# MidiWah.net
KiCad netlist of a schematic drawn in EAGLE
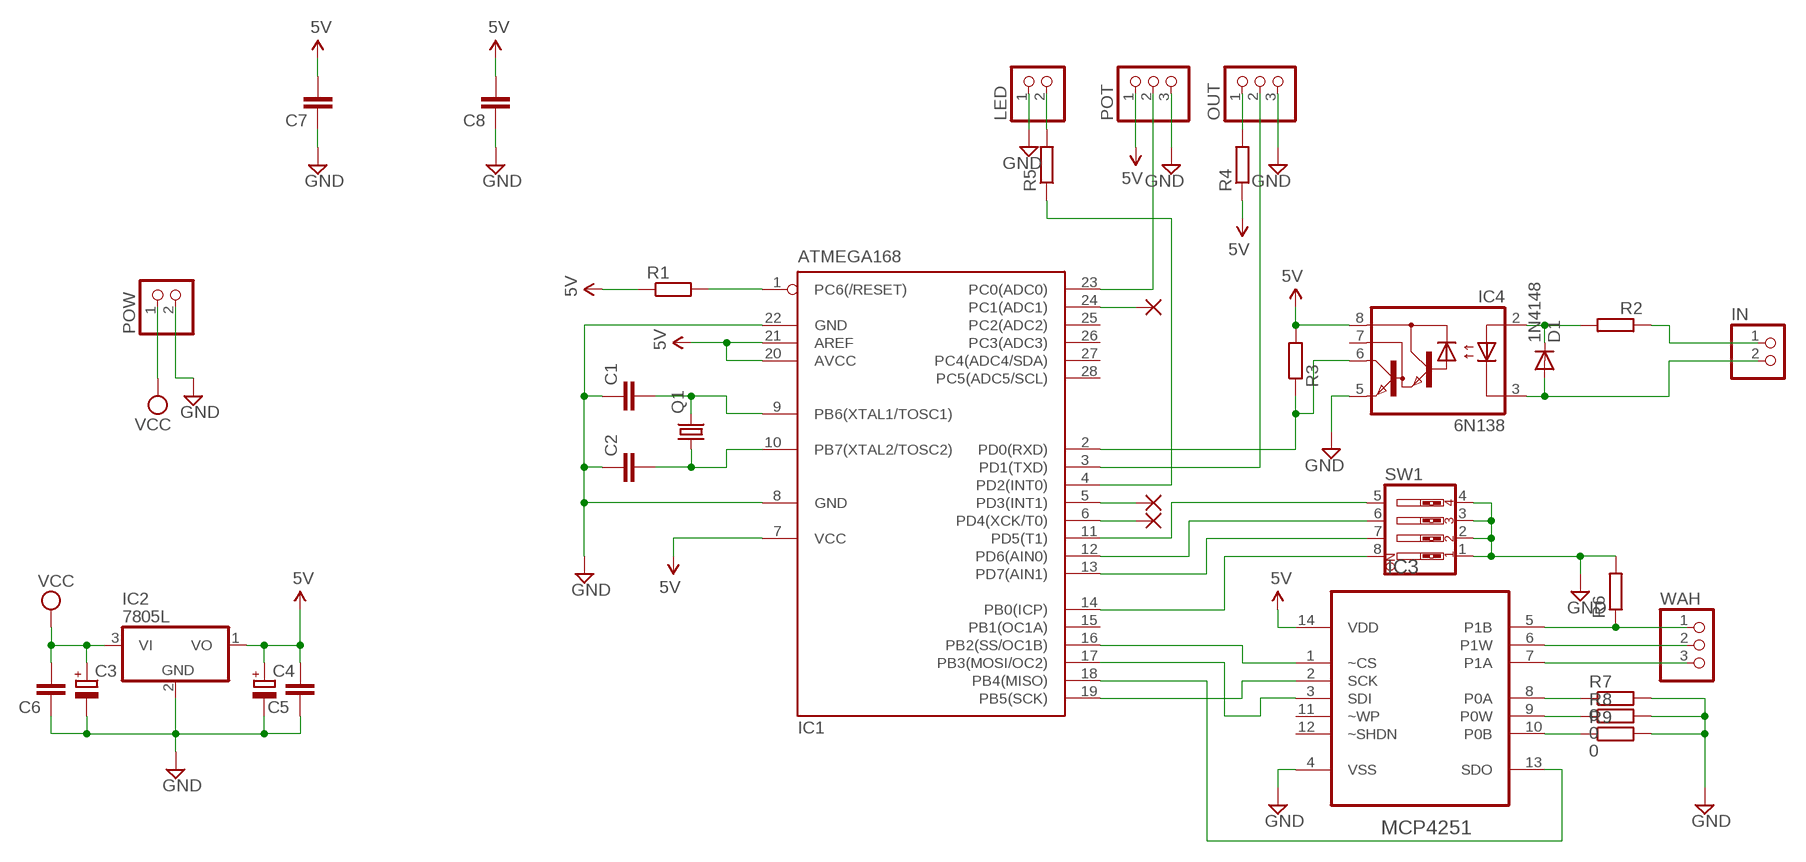
[diagram p0: schematic, sheet 1]

(export (version "E")
  (design (tool "Eeschema 10.0.6"))
  (components
    (comp (ref "C1")
      (value "C-EU025-024X044")
      (footprint "eagle-import:C025-024X044")
      (libsource (lib "eagle-import") (part "C-EU025-024X044"))
    )
    (comp (ref "C2")
      (value "C-EU025-024X044")
      (footprint "eagle-import:C025-024X044")
      (libsource (lib "eagle-import") (part "C-EU025-024X044"))
    )
    (comp (ref "C3")
      (value "CPOL-EUE2.5-5")
      (footprint "eagle-import:E2,5-5")
      (libsource (lib "eagle-import") (part "CPOL-EUE2.5-5"))
    )
    (comp (ref "C4")
      (value "CPOL-EUE2.5-5")
      (footprint "eagle-import:E2,5-5")
      (libsource (lib "eagle-import") (part "CPOL-EUE2.5-5"))
    )
    (comp (ref "C5")
      (value "C-EU025-024X044")
      (footprint "eagle-import:C025-024X044")
      (libsource (lib "eagle-import") (part "C-EU025-024X044"))
    )
    (comp (ref "C6")
      (value "C-EU025-024X044")
      (footprint "eagle-import:C025-024X044")
      (libsource (lib "eagle-import") (part "C-EU025-024X044"))
    )
    (comp (ref "C7")
      (value "C-EU025-024X044")
      (footprint "eagle-import:C025-024X044")
      (libsource (lib "eagle-import") (part "C-EU025-024X044"))
    )
    (comp (ref "C8")
      (value "C-EU025-024X044")
      (footprint "eagle-import:C025-024X044")
      (libsource (lib "eagle-import") (part "C-EU025-024X044"))
    )
    (comp (ref "D1")
      (value "1N4148")
      (footprint "eagle-import:DO35-7")
      (libsource (lib "eagle-import") (part "1N4148DO35-7"))
    )
    (comp (ref "IC1")
      (value "ATMEGA168")
      (footprint "eagle-import:DIL28-3")
      (libsource (lib "eagle-import") (part "MEGA8-P"))
    )
    (comp (ref "IC2")
      (value "7805L")
      (footprint "eagle-import:TO92")
      (libsource (lib "eagle-import") (part "78L05"))
    )
    (comp (ref "IC3")
      (value "MCP4251")
      (footprint "eagle-import:DIP254P762X533-14")
      (fields (field (name "MPN") "MCP4251-104E/P"))
      (libsource (lib "eagle-import") (part "MCP4251-104E/P"))
    )
    (comp (ref "IC4")
      (value "6N138")
      (footprint "eagle-import:DIL08")
      (fields (field (name "MF") "VISHAY/TELEFUNKEN"))
      (libsource (lib "eagle-import") (part "6N138"))
    )
    (comp (ref "IN")
      (value "PINHD-1X2")
      (footprint "eagle-import:1X02")
      (libsource (lib "eagle-import") (part "PINHD-1X2"))
    )
    (comp (ref "LED")
      (value "PINHD-1X2")
      (footprint "eagle-import:1X02")
      (libsource (lib "eagle-import") (part "PINHD-1X2"))
    )
    (comp (ref "OUT")
      (value "PINHD-1X3")
      (footprint "eagle-import:1X03")
      (libsource (lib "eagle-import") (part "PINHD-1X3"))
    )
    (comp (ref "PAD1")
      (value "WIREPAD1,6/0,8")
      (footprint "eagle-import:1,6_0,8")
      (libsource (lib "eagle-import") (part "WIREPAD1,6/0,8"))
    )
    (comp (ref "PAD2")
      (value "WIREPAD1,6/0,8")
      (footprint "eagle-import:1,6_0,8")
      (libsource (lib "eagle-import") (part "WIREPAD1,6/0,8"))
    )
    (comp (ref "PAD3")
      (value "WIREPAD1,6/0,8")
      (footprint "eagle-import:1,6_0,8")
      (libsource (lib "eagle-import") (part "WIREPAD1,6/0,8"))
    )
    (comp (ref "POT")
      (value "PINHD-1X3")
      (footprint "eagle-import:1X03")
      (libsource (lib "eagle-import") (part "PINHD-1X3"))
    )
    (comp (ref "POW")
      (value "PINHD-1X2")
      (footprint "eagle-import:1X02")
      (libsource (lib "eagle-import") (part "PINHD-1X2"))
    )
    (comp (ref "Q1")
      (value "CRYSTALHC49S")
      (footprint "eagle-import:HC49_S")
      (libsource (lib "eagle-import") (part "CRYSTALHC49S"))
    )
    (comp (ref "R1")
      (value "R-EU_0204/7")
      (footprint "eagle-import:0204_7")
      (libsource (lib "eagle-import") (part "R-EU_0204/7"))
    )
    (comp (ref "R2")
      (value "R-EU_0204/7")
      (footprint "eagle-import:0204_7")
      (libsource (lib "eagle-import") (part "R-EU_0204/7"))
    )
    (comp (ref "R3")
      (value "R-EU_0204/7")
      (footprint "eagle-import:0204_7")
      (libsource (lib "eagle-import") (part "R-EU_0204/7"))
    )
    (comp (ref "R4")
      (value "R-EU_0204/7")
      (footprint "eagle-import:0204_7")
      (libsource (lib "eagle-import") (part "R-EU_0204/7"))
    )
    (comp (ref "R5")
      (value "R-EU_0204/7")
      (footprint "eagle-import:0204_7")
      (libsource (lib "eagle-import") (part "R-EU_0204/7"))
    )
    (comp (ref "R6")
      (value "R-EU_0204/2V")
      (footprint "eagle-import:0204V")
      (libsource (lib "eagle-import") (part "R-EU_0204/2V"))
    )
    (comp (ref "R7")
      (value "0")
      (footprint "eagle-import:M0805")
      (libsource (lib "eagle-import") (part "R-EU_M0805"))
    )
    (comp (ref "R8")
      (value "0")
      (footprint "eagle-import:M0805")
      (libsource (lib "eagle-import") (part "R-EU_M0805"))
    )
    (comp (ref "R9")
      (value "0")
      (footprint "eagle-import:M0805")
      (libsource (lib "eagle-import") (part "R-EU_M0805"))
    )
    (comp (ref "SW1")
      (value "SW_DIP-4")
      (footprint "eagle-import:EDG-04")
      (libsource (lib "eagle-import") (part "SW_DIP-4"))
    )
    (comp (ref "WAH")
      (value "PINHD-1X3")
      (footprint "eagle-import:1X03")
      (libsource (lib "eagle-import") (part "PINHD-1X3"))
    )
  )
  (nets
    (net (code "1") (name "5V") (class "Default")
      (node (ref "C4") (pin "+") (pinfunction "+_+") (pintype "passive"))
      (node (ref "C5") (pin "2") (pinfunction "2_2") (pintype "passive"))
      (node (ref "C7") (pin "2") (pinfunction "2_2") (pintype "passive"))
      (node (ref "C8") (pin "2") (pinfunction "2_2") (pintype "passive"))
      (node (ref "IC1") (pin "20") (pinfunction "AVCC_20") (pintype "power_in"))
      (node (ref "IC1") (pin "21") (pinfunction "AREF_21") (pintype "passive"))
      (node (ref "IC1") (pin "7") (pinfunction "VCC_7") (pintype "power_in"))
      (node (ref "IC2") (pin "1") (pinfunction "VO_1") (pintype "passive"))
      (node (ref "IC3") (pin "14") (pinfunction "VDD_14") (pintype "power_in"))
      (node (ref "IC4") (pin "8") (pinfunction "VCC_8") (pintype "passive"))
      (node (ref "POT") (pin "1") (pinfunction "1_1") (pintype "passive"))
      (node (ref "R1") (pin "1") (pinfunction "1_1") (pintype "passive"))
      (node (ref "R3") (pin "2") (pinfunction "2_2") (pintype "passive"))
      (node (ref "R4") (pin "1") (pinfunction "1_1") (pintype "passive"))
    )
    (net (code "2") (name "GND") (class "Default")
      (node (ref "C1") (pin "1") (pinfunction "1_1") (pintype "passive"))
      (node (ref "C2") (pin "1") (pinfunction "1_1") (pintype "passive"))
      (node (ref "C3") (pin "-") (pinfunction "-_-") (pintype "passive"))
      (node (ref "C4") (pin "-") (pinfunction "-_-") (pintype "passive"))
      (node (ref "C5") (pin "1") (pinfunction "1_1") (pintype "passive"))
      (node (ref "C6") (pin "1") (pinfunction "1_1") (pintype "passive"))
      (node (ref "C7") (pin "1") (pinfunction "1_1") (pintype "passive"))
      (node (ref "C8") (pin "1") (pinfunction "1_1") (pintype "passive"))
      (node (ref "IC1") (pin "22") (pinfunction "GND_22") (pintype "power_in"))
      (node (ref "IC1") (pin "8") (pinfunction "GND_8") (pintype "power_in"))
      (node (ref "IC2") (pin "2") (pinfunction "GND_2") (pintype "passive"))
      (node (ref "IC3") (pin "4") (pinfunction "VSS_4") (pintype "power_in"))
      (node (ref "IC4") (pin "5") (pinfunction "GND_5") (pintype "passive"))
      (node (ref "LED") (pin "1") (pinfunction "1_1") (pintype "passive"))
      (node (ref "OUT") (pin "3") (pinfunction "3_3") (pintype "passive"))
      (node (ref "POT") (pin "3") (pinfunction "3_3") (pintype "passive"))
      (node (ref "POW") (pin "2") (pinfunction "2_2") (pintype "passive"))
      (node (ref "R6") (pin "2") (pinfunction "2_2") (pintype "passive"))
      (node (ref "R7") (pin "2") (pinfunction "2_2") (pintype "passive"))
      (node (ref "R8") (pin "2") (pinfunction "2_2") (pintype "passive"))
      (node (ref "R9") (pin "2") (pinfunction "2_2") (pintype "passive"))
      (node (ref "SW1") (pin "1") (pinfunction "1_1") (pintype "passive"))
      (node (ref "SW1") (pin "2") (pinfunction "2_2") (pintype "passive"))
      (node (ref "SW1") (pin "3") (pinfunction "3_3") (pintype "passive"))
      (node (ref "SW1") (pin "4") (pinfunction "4_4") (pintype "passive"))
    )
    (net (code "3") (name "Net-(IC1-PB0(ICP))") (class "Default")
      (node (ref "IC1") (pin "14") (pinfunction "PB0(ICP)_14") (pintype "bidirectional"))
      (node (ref "SW1") (pin "8") (pinfunction "8_8") (pintype "passive"))
    )
    (net (code "4") (name "Net-(IC1-PB2(SS{slash}OC1B))") (class "Default")
      (node (ref "IC1") (pin "16") (pinfunction "PB2(SS/OC1B)_16") (pintype "bidirectional"))
      (node (ref "IC3") (pin "1") (pinfunction "~{CS}_1") (pintype "input"))
    )
    (net (code "5") (name "Net-(IC1-PB3(MOSI{slash}OC2))") (class "Default")
      (node (ref "IC1") (pin "17") (pinfunction "PB3(MOSI/OC2)_17") (pintype "bidirectional"))
      (node (ref "IC3") (pin "3") (pinfunction "SDI_3") (pintype "input"))
    )
    (net (code "6") (name "Net-(IC1-PB4(MISO))") (class "Default")
      (node (ref "IC1") (pin "18") (pinfunction "PB4(MISO)_18") (pintype "bidirectional"))
      (node (ref "IC3") (pin "13") (pinfunction "SDO_13") (pintype "output"))
    )
    (net (code "7") (name "Net-(IC1-PB5(SCK))") (class "Default")
      (node (ref "IC1") (pin "19") (pinfunction "PB5(SCK)_19") (pintype "bidirectional"))
      (node (ref "IC3") (pin "2") (pinfunction "SCK_2") (pintype "input"))
    )
    (net (code "8") (name "Net-(IC1-PB6(XTAL1{slash}TOSC1))") (class "Default")
      (node (ref "C1") (pin "2") (pinfunction "2_2") (pintype "passive"))
      (node (ref "IC1") (pin "9") (pinfunction "PB6(XTAL1/TOSC1)_9") (pintype "bidirectional"))
      (node (ref "Q1") (pin "2") (pinfunction "2_2") (pintype "passive"))
    )
    (net (code "9") (name "Net-(IC1-PB7(XTAL2{slash}TOSC2))") (class "Default")
      (node (ref "C2") (pin "2") (pinfunction "2_2") (pintype "passive"))
      (node (ref "IC1") (pin "10") (pinfunction "PB7(XTAL2/TOSC2)_10") (pintype "bidirectional"))
      (node (ref "Q1") (pin "1") (pinfunction "1_1") (pintype "passive"))
    )
    (net (code "10") (name "Net-(IC1-PC0(ADC0))") (class "Default")
      (node (ref "IC1") (pin "23") (pinfunction "PC0(ADC0)_23") (pintype "bidirectional"))
      (node (ref "POT") (pin "2") (pinfunction "2_2") (pintype "passive"))
    )
    (net (code "11") (name "Net-(IC1-PC1(ADC1))") (class "Default")
      (node (ref "IC1") (pin "24") (pinfunction "PC1(ADC1)_24") (pintype "bidirectional"))
      (node (ref "PAD1") (pin "1") (pinfunction "P_1") (pintype "passive"))
    )
    (net (code "12") (name "Net-(IC1-PC6({slash}RESET))") (class "Default")
      (node (ref "IC1") (pin "1") (pinfunction "PC6(/RESET)_1") (pintype "bidirectional"))
      (node (ref "R1") (pin "2") (pinfunction "2_2") (pintype "passive"))
    )
    (net (code "13") (name "Net-(IC1-PD0(RXD))") (class "Default")
      (node (ref "IC1") (pin "2") (pinfunction "PD0(RXD)_2") (pintype "bidirectional"))
      (node (ref "IC4") (pin "6") (pinfunction "VO_6") (pintype "passive"))
      (node (ref "R3") (pin "1") (pinfunction "1_1") (pintype "passive"))
    )
    (net (code "14") (name "Net-(IC1-PD1(TXD))") (class "Default")
      (node (ref "IC1") (pin "3") (pinfunction "PD1(TXD)_3") (pintype "bidirectional"))
      (node (ref "OUT") (pin "2") (pinfunction "2_2") (pintype "passive"))
    )
    (net (code "15") (name "Net-(IC1-PD2(INT0))") (class "Default")
      (node (ref "IC1") (pin "4") (pinfunction "PD2(INT0)_4") (pintype "bidirectional"))
      (node (ref "R5") (pin "1") (pinfunction "1_1") (pintype "passive"))
    )
    (net (code "16") (name "Net-(IC1-PD3(INT1))") (class "Default")
      (node (ref "IC1") (pin "5") (pinfunction "PD3(INT1)_5") (pintype "bidirectional"))
      (node (ref "PAD2") (pin "1") (pinfunction "P_1") (pintype "passive"))
    )
    (net (code "17") (name "Net-(IC1-PD4(XCK{slash}T0))") (class "Default")
      (node (ref "IC1") (pin "6") (pinfunction "PD4(XCK/T0)_6") (pintype "bidirectional"))
      (node (ref "PAD3") (pin "1") (pinfunction "P_1") (pintype "passive"))
    )
    (net (code "18") (name "Net-(IC1-PD5(T1))") (class "Default")
      (node (ref "IC1") (pin "11") (pinfunction "PD5(T1)_11") (pintype "bidirectional"))
      (node (ref "SW1") (pin "5") (pinfunction "5_5") (pintype "passive"))
    )
    (net (code "19") (name "Net-(IC1-PD6(AIN0))") (class "Default")
      (node (ref "IC1") (pin "12") (pinfunction "PD6(AIN0)_12") (pintype "bidirectional"))
      (node (ref "SW1") (pin "6") (pinfunction "6_6") (pintype "passive"))
    )
    (net (code "20") (name "Net-(IC1-PD7(AIN1))") (class "Default")
      (node (ref "IC1") (pin "13") (pinfunction "PD7(AIN1)_13") (pintype "bidirectional"))
      (node (ref "SW1") (pin "7") (pinfunction "7_7") (pintype "passive"))
    )
    (net (code "21") (name "Net-(IC3-P0A)") (class "Default")
      (node (ref "IC3") (pin "8") (pinfunction "P0A_8") (pintype "passive"))
      (node (ref "R7") (pin "1") (pinfunction "1_1") (pintype "passive"))
    )
    (net (code "22") (name "Net-(IC3-P0B)") (class "Default")
      (node (ref "IC3") (pin "10") (pinfunction "P0B_10") (pintype "passive"))
      (node (ref "R9") (pin "1") (pinfunction "1_1") (pintype "passive"))
    )
    (net (code "23") (name "Net-(IC3-P0W)") (class "Default")
      (node (ref "IC3") (pin "9") (pinfunction "P0W_9") (pintype "passive"))
      (node (ref "R8") (pin "1") (pinfunction "1_1") (pintype "passive"))
    )
    (net (code "24") (name "Net-(IC3-P1A)") (class "Default")
      (node (ref "IC3") (pin "7") (pinfunction "P1A_7") (pintype "passive"))
      (node (ref "WAH") (pin "3") (pinfunction "3_3") (pintype "passive"))
    )
    (net (code "25") (name "Net-(IC3-P1B)") (class "Default")
      (node (ref "IC3") (pin "5") (pinfunction "P1B_5") (pintype "passive"))
      (node (ref "R6") (pin "1") (pinfunction "1_1") (pintype "passive"))
      (node (ref "WAH") (pin "1") (pinfunction "1_1") (pintype "passive"))
    )
    (net (code "26") (name "Net-(IC3-P1W)") (class "Default")
      (node (ref "IC3") (pin "6") (pinfunction "P1W_6") (pintype "passive"))
      (node (ref "WAH") (pin "2") (pinfunction "2_2") (pintype "passive"))
    )
    (net (code "27") (name "Net-(IC4-A)") (class "Default")
      (node (ref "D1") (pin "C") (pinfunction "C_C") (pintype "passive"))
      (node (ref "IC4") (pin "2") (pinfunction "A_2") (pintype "passive"))
      (node (ref "R2") (pin "2") (pinfunction "2_2") (pintype "passive"))
    )
    (net (code "28") (name "Net-(IC4-C)") (class "Default")
      (node (ref "D1") (pin "A") (pinfunction "A_A") (pintype "passive"))
      (node (ref "IC4") (pin "3") (pinfunction "C_3") (pintype "passive"))
      (node (ref "IN") (pin "2") (pinfunction "2_2") (pintype "passive"))
    )
    (net (code "29") (name "Net-(IN-Pad1)") (class "Default")
      (node (ref "IN") (pin "1") (pinfunction "1_1") (pintype "passive"))
      (node (ref "R2") (pin "1") (pinfunction "1_1") (pintype "passive"))
    )
    (net (code "30") (name "Net-(LED-Pad2)") (class "Default")
      (node (ref "LED") (pin "2") (pinfunction "2_2") (pintype "passive"))
      (node (ref "R5") (pin "2") (pinfunction "2_2") (pintype "passive"))
    )
    (net (code "31") (name "Net-(OUT-Pad1)") (class "Default")
      (node (ref "OUT") (pin "1") (pinfunction "1_1") (pintype "passive"))
      (node (ref "R4") (pin "2") (pinfunction "2_2") (pintype "passive"))
    )
    (net (code "32") (name "VCC") (class "Default")
      (node (ref "C3") (pin "+") (pinfunction "+_+") (pintype "passive"))
      (node (ref "C6") (pin "2") (pinfunction "2_2") (pintype "passive"))
      (node (ref "IC2") (pin "3") (pinfunction "VI_3") (pintype "input"))
      (node (ref "POW") (pin "1") (pinfunction "1_1") (pintype "passive"))
    )
    (net (code "33") (name "unconnected-(IC1-PB1(OC1A)-Pad15)") (class "Default")
      (node (ref "IC1") (pin "15") (pinfunction "PB1(OC1A)_15") (pintype "bidirectional"))
    )
    (net (code "34") (name "unconnected-(IC1-PC2(ADC2)-Pad25)") (class "Default")
      (node (ref "IC1") (pin "25") (pinfunction "PC2(ADC2)_25") (pintype "bidirectional"))
    )
    (net (code "35") (name "unconnected-(IC1-PC3(ADC3)-Pad26)") (class "Default")
      (node (ref "IC1") (pin "26") (pinfunction "PC3(ADC3)_26") (pintype "bidirectional"))
    )
    (net (code "36") (name "unconnected-(IC1-PC4(ADC4{slash}SDA)-Pad27)") (class "Default")
      (node (ref "IC1") (pin "27") (pinfunction "PC4(ADC4/SDA)_27") (pintype "bidirectional"))
    )
    (net (code "37") (name "unconnected-(IC1-PC5(ADC5{slash}SCL)-Pad28)") (class "Default")
      (node (ref "IC1") (pin "28") (pinfunction "PC5(ADC5/SCL)_28") (pintype "bidirectional"))
    )
    (net (code "38") (name "unconnected-(IC3-~{SHDN}-Pad12)") (class "Default")
      (node (ref "IC3") (pin "12") (pinfunction "~{SHDN}_12") (pintype "input"))
    )
    (net (code "39") (name "unconnected-(IC3-~{WP}-Pad11)") (class "Default")
      (node (ref "IC3") (pin "11") (pinfunction "~{WP}_11") (pintype "input"))
    )
    (net (code "40") (name "unconnected-(IC4-VB-Pad7)") (class "Default")
      (node (ref "IC4") (pin "7") (pinfunction "VB_7") (pintype "passive"))
    )
  )
)
